# LCD_Connectors.net
KiCad netlist of a schematic drawn in Altium Designer
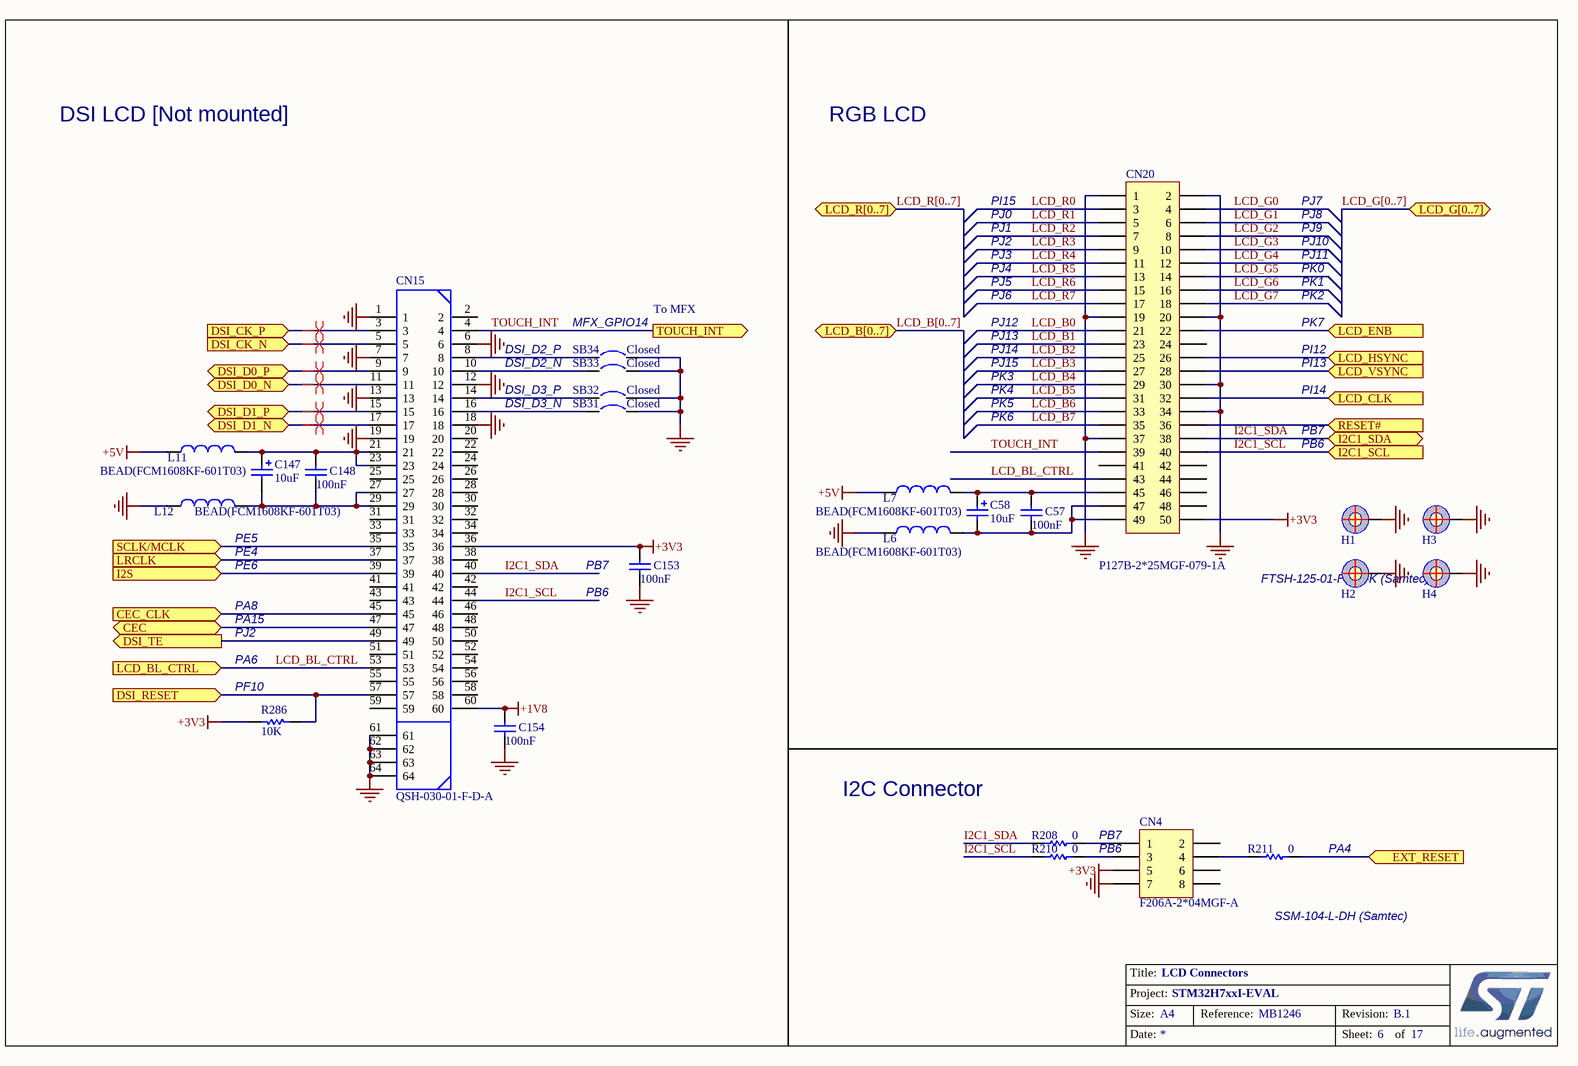
[diagram p0: LCD Connectors.SchDoc]

(export (version "E")
  (design (tool "Eeschema 10.0.6"))
  (components
    (comp (ref "C57")
      (value "100nF")
      (footprint "0603C")
      (description "Capacitor")
      (fields (field (name "PUBLISHER") "Altium Limited"))
      (libsource (lib "Miscellaneous Devices") (part "Cap"))
    )
    (comp (ref "C58")
      (value "10uF")
      (footprint "TAN-A")
      (description "Polarized Capacitor (Radial)")
      (fields (field (name "PUBLISHER") "Altium Limited"))
      (libsource (lib "Miscellaneous Devices") (part "Cap Pol1"))
    )
    (comp (ref "C147")
      (value "10uF")
      (footprint "TAN-A")
      (description "Polarized Capacitor (Radial)")
      (fields (field (name "PUBLISHER") "Altium Limited"))
      (libsource (lib "Miscellaneous Devices") (part "Cap Pol1"))
    )
    (comp (ref "C148")
      (value "100nF")
      (footprint "0603C")
      (description "Capacitor")
      (fields (field (name "PUBLISHER") "Altium Limited"))
      (libsource (lib "Miscellaneous Devices") (part "Cap"))
    )
    (comp (ref "C153")
      (value "100nF")
      (footprint "0603C")
      (description "Capacitor")
      (fields (field (name "PUBLISHER") "Altium Limited"))
      (libsource (lib "Miscellaneous Devices") (part "Cap"))
    )
    (comp (ref "C154")
      (value "100nF")
      (footprint "0603C")
      (description "Capacitor")
      (fields (field (name "PUBLISHER") "Altium Limited"))
      (libsource (lib "Miscellaneous Devices") (part "Cap"))
    )
    (comp (ref "CN4")
      (value "F206A-2*04MGF-A")
      (footprint "SSM-104-L-DH")
      (description "Header, 5-Pin, Dual row")
      (fields (field (name "PUBLISHER") "Altium Limited"))
      (libsource (lib "mb1045") (part "SSM-104-L-DH"))
    )
    (comp (ref "CN15")
      (value "QSH-030-01-F-D-A")
      (footprint "QSH-030-01-F-D-A")
      (description "HIGH SPEED SOCKET STRIP, .5mm PITCH, 60 PINS")
      (fields (field (name "MANUFACTURER") "SAMTEC") (field (name "CREATED") "28 JAN 2014 - WENDY XIN"))
      (libsource (lib "MB1166") (part "QSH-030-01-F-D-A"))
    )
    (comp (ref "CN20")
      (value "P127B-2*25MGF-079-1A")
      (footprint "FTSH-125-01-F-DV")
      (description "Header, 26-Pin, Dual row")
      (fields (field (name "PUBLISHER") "Altium Limited"))
      (libsource (lib "mb1045") (part "Header 25X2"))
    )
    (comp (ref "H1")
      (value "POSITION HOLE")
      (footprint "HOLE_C9D4R5")
      (libsource (lib "mb1045") (part "POSITION HOLE"))
    )
    (comp (ref "H2")
      (value "POSITION HOLE")
      (footprint "HOLE_C9D4R5")
      (libsource (lib "mb1045") (part "POSITION HOLE"))
    )
    (comp (ref "H3")
      (value "POSITION HOLE")
      (footprint "HOLE_C9D4R5")
      (libsource (lib "mb1045") (part "POSITION HOLE"))
    )
    (comp (ref "H4")
      (value "POSITION HOLE")
      (footprint "HOLE_C9D4R5")
      (libsource (lib "mb1045") (part "POSITION HOLE"))
    )
    (comp (ref "L6")
      (value "BEAD(FCM1608KF-601T03)")
      (footprint "0603L")
      (description "Inductor")
      (fields (field (name "PUBLISHER") "Altium Limited"))
      (libsource (lib "Miscellaneous Devices") (part "Inductor"))
    )
    (comp (ref "L7")
      (value "BEAD(FCM1608KF-601T03)")
      (footprint "0603L")
      (description "Inductor")
      (fields (field (name "PUBLISHER") "Altium Limited"))
      (libsource (lib "Miscellaneous Devices") (part "Inductor"))
    )
    (comp (ref "L11")
      (value "BEAD(FCM1608KF-601T03)")
      (footprint "0603L")
      (description "Inductor")
      (fields (field (name "PUBLISHER") "Altium Limited"))
      (libsource (lib "Miscellaneous Devices") (part "Inductor"))
    )
    (comp (ref "L12")
      (value "BEAD(FCM1608KF-601T03)")
      (footprint "0603L")
      (description "Inductor")
      (fields (field (name "PUBLISHER") "Altium Limited"))
      (libsource (lib "Miscellaneous Devices") (part "Inductor"))
    )
    (comp (ref "R208")
      (value "0")
      (footprint "0603R")
      (description "Resistor")
      (fields (field (name "PUBLISHER") "Altium Limited"))
      (libsource (lib "Miscellaneous Devices") (part "Res1"))
    )
    (comp (ref "R210")
      (value "0")
      (footprint "0603R")
      (description "Resistor")
      (fields (field (name "PUBLISHER") "Altium Limited"))
      (libsource (lib "Miscellaneous Devices") (part "Res1"))
    )
    (comp (ref "R211")
      (value "0")
      (footprint "0603R")
      (description "Resistor")
      (fields (field (name "PUBLISHER") "Altium Limited"))
      (libsource (lib "Miscellaneous Devices") (part "Res1"))
    )
    (comp (ref "R286")
      (value "10K")
      (footprint "0603R")
      (description "Resistor")
      (fields (field (name "PUBLISHER") "Altium Limited"))
      (libsource (lib "") (part "Res1_1"))
    )
    (comp (ref "SB31")
      (value "Closed")
      (footprint "SB_0603")
      (description "Circuit Breaker")
      (fields (field (name "PUBLISHER") "Altium Limited"))
      (libsource (lib "MB1165") (part "Circuit Breaker_close"))
    )
    (comp (ref "SB32")
      (value "Closed")
      (footprint "SB_0603")
      (description "Circuit Breaker")
      (fields (field (name "PUBLISHER") "Altium Limited"))
      (libsource (lib "MB1165") (part "Circuit Breaker_close"))
    )
    (comp (ref "SB33")
      (value "Closed")
      (footprint "SB_0603")
      (description "Circuit Breaker")
      (fields (field (name "PUBLISHER") "Altium Limited"))
      (libsource (lib "MB1165") (part "Circuit Breaker_close"))
    )
    (comp (ref "SB34")
      (value "Closed")
      (footprint "SB_0603")
      (description "Circuit Breaker")
      (fields (field (name "PUBLISHER") "Altium Limited"))
      (libsource (lib "MB1165") (part "Circuit Breaker_close"))
    )
  )
  (nets
    (net (code "1") (name "+1V8") (class "Default")
      (node (ref "C154") (pin "1") (pinfunction "1_1") (pintype "passive"))
      (node (ref "CN15") (pin "60") (pinfunction "60_60") (pintype "passive"))
    )
    (net (code "2") (name "+3V3") (class "Default")
      (node (ref "C153") (pin "1") (pinfunction "1_1") (pintype "passive"))
      (node (ref "CN15") (pin "36") (pinfunction "36_36") (pintype "passive"))
      (node (ref "CN20") (pin "50") (pinfunction "50_50") (pintype "passive"))
      (node (ref "CN4") (pin "5") (pinfunction "5_5") (pintype "passive"))
      (node (ref "R286") (pin "2") (pinfunction "2_2") (pintype "passive"))
    )
    (net (code "3") (name "+5V") (class "Default")
      (node (ref "L11") (pin "1") (pinfunction "1_1") (pintype "passive"))
      (node (ref "L7") (pin "1") (pinfunction "1_1") (pintype "passive"))
    )
    (net (code "4") (name "/CEC") (class "Default")
      (node (ref "CN15") (pin "47") (pinfunction "47_47") (pintype "passive"))
    )
    (net (code "5") (name "/CEC_CLK") (class "Default")
      (node (ref "CN15") (pin "45") (pinfunction "45_45") (pintype "passive"))
    )
    (net (code "6") (name "/DSI_CK_N") (class "Default")
      (node (ref "CN15") (pin "5") (pinfunction "5_5") (pintype "passive"))
    )
    (net (code "7") (name "/DSI_CK_P") (class "Default")
      (node (ref "CN15") (pin "3") (pinfunction "3_3") (pintype "passive"))
    )
    (net (code "8") (name "/DSI_D0_N") (class "Default")
      (node (ref "CN15") (pin "11") (pinfunction "11_11") (pintype "passive"))
    )
    (net (code "9") (name "/DSI_D0_P") (class "Default")
      (node (ref "CN15") (pin "9") (pinfunction "9_9") (pintype "passive"))
    )
    (net (code "10") (name "/DSI_D1_N") (class "Default")
      (node (ref "CN15") (pin "17") (pinfunction "17_17") (pintype "passive"))
    )
    (net (code "11") (name "/DSI_D1_P") (class "Default")
      (node (ref "CN15") (pin "15") (pinfunction "15_15") (pintype "passive"))
    )
    (net (code "12") (name "/DSI_RESET") (class "Default")
      (node (ref "CN15") (pin "57") (pinfunction "57_57") (pintype "passive"))
      (node (ref "R286") (pin "1") (pinfunction "1_1") (pintype "passive"))
    )
    (net (code "13") (name "/DSI_TE") (class "Default")
      (node (ref "CN15") (pin "49") (pinfunction "49_49") (pintype "passive"))
    )
    (net (code "14") (name "/EXT_RESET") (class "Default")
      (node (ref "R211") (pin "2") (pinfunction "2_2") (pintype "passive"))
    )
    (net (code "15") (name "/I2C1_SCL") (class "Default")
      (node (ref "CN15") (pin "44") (pinfunction "44_44") (pintype "passive"))
      (node (ref "CN20") (pin "40") (pinfunction "40_40") (pintype "passive"))
      (node (ref "R210") (pin "1") (pinfunction "1_1") (pintype "passive"))
    )
    (net (code "16") (name "/I2C1_SDA") (class "Default")
      (node (ref "CN15") (pin "40") (pinfunction "40_40") (pintype "passive"))
      (node (ref "CN20") (pin "38") (pinfunction "38_38") (pintype "passive"))
      (node (ref "R208") (pin "1") (pinfunction "1_1") (pintype "passive"))
    )
    (net (code "17") (name "/I2S") (class "Default")
      (node (ref "CN15") (pin "39") (pinfunction "39_39") (pintype "passive"))
    )
    (net (code "18") (name "/LCD_B0") (class "Default")
      (node (ref "CN20") (pin "21") (pinfunction "21_21") (pintype "passive"))
    )
    (net (code "19") (name "/LCD_B1") (class "Default")
      (node (ref "CN20") (pin "23") (pinfunction "23_23") (pintype "passive"))
    )
    (net (code "20") (name "/LCD_B2") (class "Default")
      (node (ref "CN20") (pin "25") (pinfunction "25_25") (pintype "passive"))
    )
    (net (code "21") (name "/LCD_B3") (class "Default")
      (node (ref "CN20") (pin "27") (pinfunction "27_27") (pintype "passive"))
    )
    (net (code "22") (name "/LCD_B4") (class "Default")
      (node (ref "CN20") (pin "29") (pinfunction "29_29") (pintype "passive"))
    )
    (net (code "23") (name "/LCD_B5") (class "Default")
      (node (ref "CN20") (pin "31") (pinfunction "31_31") (pintype "passive"))
    )
    (net (code "24") (name "/LCD_B6") (class "Default")
      (node (ref "CN20") (pin "33") (pinfunction "33_33") (pintype "passive"))
    )
    (net (code "25") (name "/LCD_B7") (class "Default")
      (node (ref "CN20") (pin "35") (pinfunction "35_35") (pintype "passive"))
    )
    (net (code "26") (name "/LCD_BL_CTRL") (class "Default")
      (node (ref "CN15") (pin "53") (pinfunction "53_53") (pintype "passive"))
      (node (ref "CN20") (pin "43") (pinfunction "43_43") (pintype "passive"))
    )
    (net (code "28") (name "/LCD_CLK") (class "Default")
      (node (ref "CN20") (pin "32") (pinfunction "32_32") (pintype "passive"))
    )
    (net (code "29") (name "/LCD_ENB") (class "Default")
      (node (ref "CN20") (pin "22") (pinfunction "22_22") (pintype "passive"))
    )
    (net (code "30") (name "/LCD_G0") (class "Default")
      (node (ref "CN20") (pin "4") (pinfunction "4_4") (pintype "passive"))
    )
    (net (code "31") (name "/LCD_G1") (class "Default")
      (node (ref "CN20") (pin "6") (pinfunction "6_6") (pintype "passive"))
    )
    (net (code "32") (name "/LCD_G2") (class "Default")
      (node (ref "CN20") (pin "8") (pinfunction "8_8") (pintype "passive"))
    )
    (net (code "33") (name "/LCD_G3") (class "Default")
      (node (ref "CN20") (pin "10") (pinfunction "10_10") (pintype "passive"))
    )
    (net (code "34") (name "/LCD_G4") (class "Default")
      (node (ref "CN20") (pin "12") (pinfunction "12_12") (pintype "passive"))
    )
    (net (code "35") (name "/LCD_G5") (class "Default")
      (node (ref "CN20") (pin "14") (pinfunction "14_14") (pintype "passive"))
    )
    (net (code "36") (name "/LCD_G6") (class "Default")
      (node (ref "CN20") (pin "16") (pinfunction "16_16") (pintype "passive"))
    )
    (net (code "37") (name "/LCD_G7") (class "Default")
      (node (ref "CN20") (pin "18") (pinfunction "18_18") (pintype "passive"))
    )
    (net (code "39") (name "/LCD_HSYNC") (class "Default")
      (node (ref "CN20") (pin "26") (pinfunction "26_26") (pintype "passive"))
    )
    (net (code "40") (name "/LCD_R0") (class "Default")
      (node (ref "CN20") (pin "3") (pinfunction "3_3") (pintype "passive"))
    )
    (net (code "41") (name "/LCD_R1") (class "Default")
      (node (ref "CN20") (pin "5") (pinfunction "5_5") (pintype "passive"))
    )
    (net (code "42") (name "/LCD_R2") (class "Default")
      (node (ref "CN20") (pin "7") (pinfunction "7_7") (pintype "passive"))
    )
    (net (code "43") (name "/LCD_R3") (class "Default")
      (node (ref "CN20") (pin "9") (pinfunction "9_9") (pintype "passive"))
    )
    (net (code "44") (name "/LCD_R4") (class "Default")
      (node (ref "CN20") (pin "11") (pinfunction "11_11") (pintype "passive"))
    )
    (net (code "45") (name "/LCD_R5") (class "Default")
      (node (ref "CN20") (pin "13") (pinfunction "13_13") (pintype "passive"))
    )
    (net (code "46") (name "/LCD_R6") (class "Default")
      (node (ref "CN20") (pin "15") (pinfunction "15_15") (pintype "passive"))
    )
    (net (code "47") (name "/LCD_R7") (class "Default")
      (node (ref "CN20") (pin "17") (pinfunction "17_17") (pintype "passive"))
    )
    (net (code "49") (name "/LCD_VSYNC") (class "Default")
      (node (ref "CN20") (pin "28") (pinfunction "28_28") (pintype "passive"))
    )
    (net (code "50") (name "/LRCLK") (class "Default")
      (node (ref "CN15") (pin "37") (pinfunction "37_37") (pintype "passive"))
    )
    (net (code "51") (name "/RESET#") (class "Default")
      (node (ref "CN20") (pin "36") (pinfunction "36_36") (pintype "passive"))
    )
    (net (code "52") (name "/SCLK{slash}MCLK") (class "Default")
      (node (ref "CN15") (pin "35") (pinfunction "35_35") (pintype "passive"))
    )
    (net (code "53") (name "/TOUCH_INT") (class "Default")
      (node (ref "CN15") (pin "4") (pinfunction "4_4") (pintype "passive"))
      (node (ref "CN20") (pin "39") (pinfunction "39_39") (pintype "passive"))
    )
    (net (code "54") (name "GND") (class "Default")
      (node (ref "C153") (pin "2") (pinfunction "2_2") (pintype "passive"))
      (node (ref "C154") (pin "2") (pinfunction "2_2") (pintype "passive"))
      (node (ref "CN15") (pin "1") (pinfunction "1_1") (pintype "passive"))
      (node (ref "CN15") (pin "12") (pinfunction "12_12") (pintype "passive"))
      (node (ref "CN15") (pin "13") (pinfunction "13_13") (pintype "passive"))
      (node (ref "CN15") (pin "18") (pinfunction "18_18") (pintype "passive"))
      (node (ref "CN15") (pin "19") (pinfunction "19_19") (pintype "passive"))
      (node (ref "CN15") (pin "6") (pinfunction "6_6") (pintype "passive"))
      (node (ref "CN15") (pin "61") (pinfunction "61_61") (pintype "passive"))
      (node (ref "CN15") (pin "62") (pinfunction "62_62") (pintype "passive"))
      (node (ref "CN15") (pin "63") (pinfunction "63_63") (pintype "passive"))
      (node (ref "CN15") (pin "64") (pinfunction "64_64") (pintype "passive"))
      (node (ref "CN15") (pin "7") (pinfunction "7_7") (pintype "passive"))
      (node (ref "CN20") (pin "1") (pinfunction "1_1") (pintype "passive"))
      (node (ref "CN20") (pin "19") (pinfunction "19_19") (pintype "passive"))
      (node (ref "CN20") (pin "2") (pinfunction "2_2") (pintype "passive"))
      (node (ref "CN20") (pin "20") (pinfunction "20_20") (pintype "passive"))
      (node (ref "CN20") (pin "30") (pinfunction "30_30") (pintype "passive"))
      (node (ref "CN20") (pin "34") (pinfunction "34_34") (pintype "passive"))
      (node (ref "CN20") (pin "37") (pinfunction "37_37") (pintype "passive"))
      (node (ref "CN4") (pin "7") (pinfunction "7_7") (pintype "passive"))
      (node (ref "H1") (pin "1") (pinfunction "1_1") (pintype "passive"))
      (node (ref "H2") (pin "1") (pinfunction "1_1") (pintype "passive"))
      (node (ref "H3") (pin "1") (pinfunction "1_1") (pintype "passive"))
      (node (ref "H4") (pin "1") (pinfunction "1_1") (pintype "passive"))
      (node (ref "L12") (pin "1") (pinfunction "1_1") (pintype "passive"))
      (node (ref "L6") (pin "1") (pinfunction "1_1") (pintype "passive"))
      (node (ref "SB31") (pin "2") (pinfunction "2_2") (pintype "passive"))
      (node (ref "SB32") (pin "2") (pinfunction "2_2") (pintype "passive"))
      (node (ref "SB33") (pin "2") (pinfunction "2_2") (pintype "passive"))
      (node (ref "SB34") (pin "2") (pinfunction "2_2") (pintype "passive"))
    )
    (net (code "55") (name "Net-(C57-Pad1)") (class "Default")
      (node (ref "C57") (pin "1") (pinfunction "1_1") (pintype "passive"))
      (node (ref "C58") (pin "1") (pinfunction "1_1") (pintype "passive"))
      (node (ref "CN20") (pin "45") (pinfunction "45_45") (pintype "passive"))
      (node (ref "L7") (pin "2") (pinfunction "2_2") (pintype "passive"))
    )
    (net (code "56") (name "Net-(C57-Pad2)") (class "Default")
      (node (ref "C57") (pin "2") (pinfunction "2_2") (pintype "passive"))
      (node (ref "C58") (pin "2") (pinfunction "2_2") (pintype "passive"))
      (node (ref "CN20") (pin "47") (pinfunction "47_47") (pintype "passive"))
      (node (ref "CN20") (pin "49") (pinfunction "49_49") (pintype "passive"))
      (node (ref "L6") (pin "2") (pinfunction "2_2") (pintype "passive"))
    )
    (net (code "57") (name "Net-(C147-Pad1)") (class "Default")
      (node (ref "C147") (pin "1") (pinfunction "1_1") (pintype "passive"))
      (node (ref "C148") (pin "1") (pinfunction "1_1") (pintype "passive"))
      (node (ref "CN15") (pin "21") (pinfunction "21_21") (pintype "passive"))
      (node (ref "CN15") (pin "23") (pinfunction "23_23") (pintype "passive"))
      (node (ref "L11") (pin "2") (pinfunction "2_2") (pintype "passive"))
    )
    (net (code "58") (name "Net-(C147-Pad2)") (class "Default")
      (node (ref "C147") (pin "2") (pinfunction "2_2") (pintype "passive"))
      (node (ref "C148") (pin "2") (pinfunction "2_2") (pintype "passive"))
      (node (ref "CN15") (pin "27") (pinfunction "27_27") (pintype "passive"))
      (node (ref "CN15") (pin "29") (pinfunction "29_29") (pintype "passive"))
      (node (ref "L12") (pin "2") (pinfunction "2_2") (pintype "passive"))
    )
    (net (code "59") (name "Net-(CN4-Pad1)") (class "Default")
      (node (ref "CN4") (pin "1") (pinfunction "1_1") (pintype "passive"))
      (node (ref "R208") (pin "2") (pinfunction "2_2") (pintype "passive"))
    )
    (net (code "60") (name "Net-(CN4-Pad3)") (class "Default")
      (node (ref "CN4") (pin "3") (pinfunction "3_3") (pintype "passive"))
      (node (ref "R210") (pin "2") (pinfunction "2_2") (pintype "passive"))
    )
    (net (code "61") (name "Net-(CN4-Pad4)") (class "Default")
      (node (ref "CN4") (pin "4") (pinfunction "4_4") (pintype "passive"))
      (node (ref "R211") (pin "1") (pinfunction "1_1") (pintype "passive"))
    )
    (net (code "62") (name "Net-(CN15-Pad8)") (class "Default")
      (node (ref "CN15") (pin "8") (pinfunction "8_8") (pintype "passive"))
      (node (ref "SB34") (pin "1") (pinfunction "1_1") (pintype "passive"))
    )
    (net (code "63") (name "Net-(CN15-Pad10)") (class "Default")
      (node (ref "CN15") (pin "10") (pinfunction "10_10") (pintype "passive"))
      (node (ref "SB33") (pin "1") (pinfunction "1_1") (pintype "passive"))
    )
    (net (code "64") (name "Net-(CN15-Pad14)") (class "Default")
      (node (ref "CN15") (pin "14") (pinfunction "14_14") (pintype "passive"))
      (node (ref "SB32") (pin "1") (pinfunction "1_1") (pintype "passive"))
    )
    (net (code "65") (name "Net-(CN15-Pad16)") (class "Default")
      (node (ref "CN15") (pin "16") (pinfunction "16_16") (pintype "passive"))
      (node (ref "SB31") (pin "1") (pinfunction "1_1") (pintype "passive"))
    )
    (net (code "66") (name "unconnected-(CN4-Pad2)") (class "Default")
      (node (ref "CN4") (pin "2") (pinfunction "2_2") (pintype "passive"))
    )
    (net (code "67") (name "unconnected-(CN4-Pad6)") (class "Default")
      (node (ref "CN4") (pin "6") (pinfunction "6_6") (pintype "passive"))
    )
    (net (code "68") (name "unconnected-(CN4-Pad8)") (class "Default")
      (node (ref "CN4") (pin "8") (pinfunction "8_8") (pintype "passive"))
    )
    (net (code "69") (name "unconnected-(CN15-Pad2)") (class "Default")
      (node (ref "CN15") (pin "2") (pinfunction "2_2") (pintype "passive"))
    )
    (net (code "70") (name "unconnected-(CN15-Pad20)") (class "Default")
      (node (ref "CN15") (pin "20") (pinfunction "20_20") (pintype "passive"))
    )
    (net (code "71") (name "unconnected-(CN15-Pad22)") (class "Default")
      (node (ref "CN15") (pin "22") (pinfunction "22_22") (pintype "passive"))
    )
    (net (code "72") (name "unconnected-(CN15-Pad24)") (class "Default")
      (node (ref "CN15") (pin "24") (pinfunction "24_24") (pintype "passive"))
    )
    (net (code "73") (name "unconnected-(CN15-Pad25)") (class "Default")
      (node (ref "CN15") (pin "25") (pinfunction "25_25") (pintype "passive"))
    )
    (net (code "74") (name "unconnected-(CN15-Pad26)") (class "Default")
      (node (ref "CN15") (pin "26") (pinfunction "26_26") (pintype "passive"))
    )
    (net (code "75") (name "unconnected-(CN15-Pad28)") (class "Default")
      (node (ref "CN15") (pin "28") (pinfunction "28_28") (pintype "passive"))
    )
    (net (code "76") (name "unconnected-(CN15-Pad30)") (class "Default")
      (node (ref "CN15") (pin "30") (pinfunction "30_30") (pintype "passive"))
    )
    (net (code "77") (name "unconnected-(CN15-Pad31)") (class "Default")
      (node (ref "CN15") (pin "31") (pinfunction "31_31") (pintype "passive"))
    )
    (net (code "78") (name "unconnected-(CN15-Pad32)") (class "Default")
      (node (ref "CN15") (pin "32") (pinfunction "32_32") (pintype "passive"))
    )
    (net (code "79") (name "unconnected-(CN15-Pad33)") (class "Default")
      (node (ref "CN15") (pin "33") (pinfunction "33_33") (pintype "passive"))
    )
    (net (code "80") (name "unconnected-(CN15-Pad34)") (class "Default")
      (node (ref "CN15") (pin "34") (pinfunction "34_34") (pintype "passive"))
    )
    (net (code "81") (name "unconnected-(CN15-Pad38)") (class "Default")
      (node (ref "CN15") (pin "38") (pinfunction "38_38") (pintype "passive"))
    )
    (net (code "82") (name "unconnected-(CN15-Pad41)") (class "Default")
      (node (ref "CN15") (pin "41") (pinfunction "41_41") (pintype "passive"))
    )
    (net (code "83") (name "unconnected-(CN15-Pad42)") (class "Default")
      (node (ref "CN15") (pin "42") (pinfunction "42_42") (pintype "passive"))
    )
    (net (code "84") (name "unconnected-(CN15-Pad43)") (class "Default")
      (node (ref "CN15") (pin "43") (pinfunction "43_43") (pintype "passive"))
    )
    (net (code "85") (name "unconnected-(CN15-Pad46)") (class "Default")
      (node (ref "CN15") (pin "46") (pinfunction "46_46") (pintype "passive"))
    )
    (net (code "86") (name "unconnected-(CN15-Pad48)") (class "Default")
      (node (ref "CN15") (pin "48") (pinfunction "48_48") (pintype "passive"))
    )
    (net (code "87") (name "unconnected-(CN15-Pad50)") (class "Default")
      (node (ref "CN15") (pin "50") (pinfunction "50_50") (pintype "passive"))
    )
    (net (code "88") (name "unconnected-(CN15-Pad51)") (class "Default")
      (node (ref "CN15") (pin "51") (pinfunction "51_51") (pintype "passive"))
    )
    (net (code "89") (name "unconnected-(CN15-Pad52)") (class "Default")
      (node (ref "CN15") (pin "52") (pinfunction "52_52") (pintype "passive"))
    )
    (net (code "90") (name "unconnected-(CN15-Pad54)") (class "Default")
      (node (ref "CN15") (pin "54") (pinfunction "54_54") (pintype "passive"))
    )
    (net (code "91") (name "unconnected-(CN15-Pad55)") (class "Default")
      (node (ref "CN15") (pin "55") (pinfunction "55_55") (pintype "passive"))
    )
    (net (code "92") (name "unconnected-(CN15-Pad56)") (class "Default")
      (node (ref "CN15") (pin "56") (pinfunction "56_56") (pintype "passive"))
    )
    (net (code "93") (name "unconnected-(CN15-Pad58)") (class "Default")
      (node (ref "CN15") (pin "58") (pinfunction "58_58") (pintype "passive"))
    )
    (net (code "94") (name "unconnected-(CN15-Pad59)") (class "Default")
      (node (ref "CN15") (pin "59") (pinfunction "59_59") (pintype "passive"))
    )
    (net (code "95") (name "unconnected-(CN20-Pad24)") (class "Default")
      (node (ref "CN20") (pin "24") (pinfunction "24_24") (pintype "passive"))
    )
    (net (code "96") (name "unconnected-(CN20-Pad41)") (class "Default")
      (node (ref "CN20") (pin "41") (pinfunction "41_41") (pintype "passive"))
    )
    (net (code "97") (name "unconnected-(CN20-Pad42)") (class "Default")
      (node (ref "CN20") (pin "42") (pinfunction "42_42") (pintype "passive"))
    )
    (net (code "98") (name "unconnected-(CN20-Pad44)") (class "Default")
      (node (ref "CN20") (pin "44") (pinfunction "44_44") (pintype "passive"))
    )
    (net (code "99") (name "unconnected-(CN20-Pad46)") (class "Default")
      (node (ref "CN20") (pin "46") (pinfunction "46_46") (pintype "passive"))
    )
    (net (code "100") (name "unconnected-(CN20-Pad48)") (class "Default")
      (node (ref "CN20") (pin "48") (pinfunction "48_48") (pintype "passive"))
    )
  )
)
